# IR.net
KiCad netlist of a schematic drawn in Altium Designer
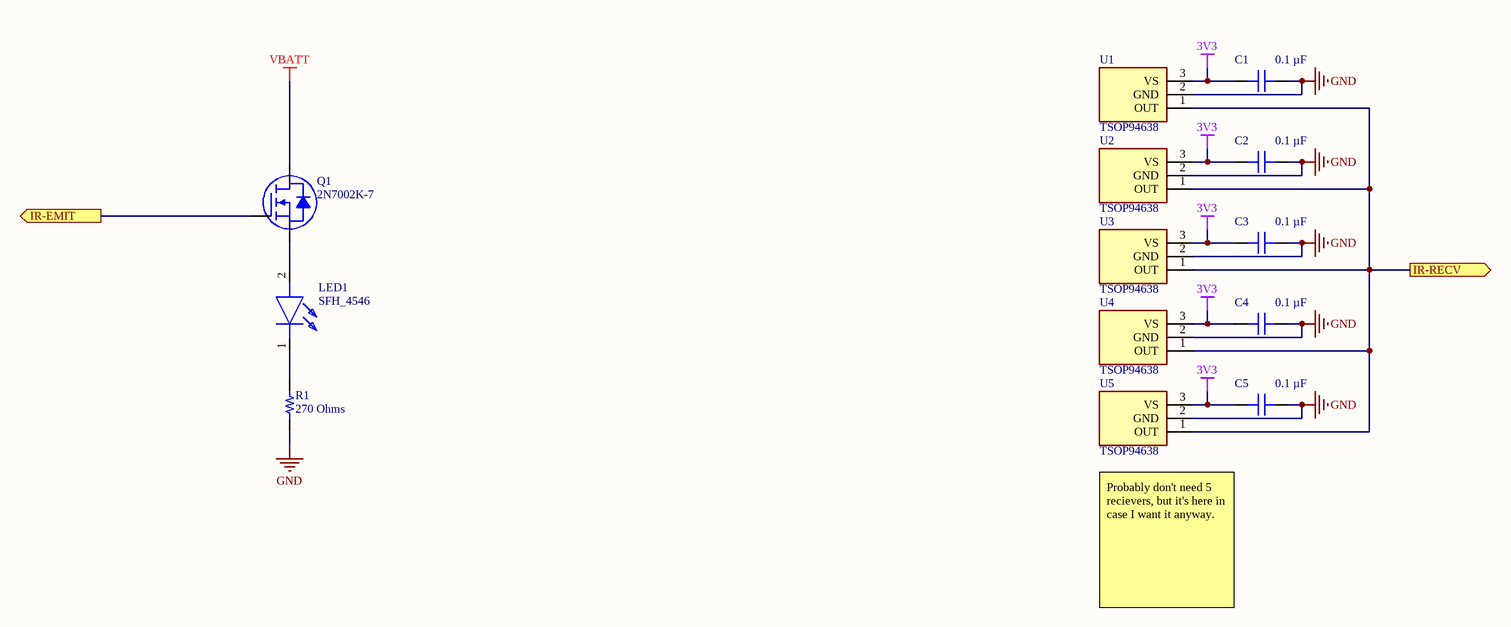
[diagram p0: IR.SchDoc]

(export (version "E")
  (design (tool "Eeschema 10.0.6"))
  (components
    (comp (ref "C1")
      (value "0.1 µF")
      (footprint "CAP 0805_2012")
      (description "CAP CER 0.1UF 25V X7R 0805")
      (fields
        (field (name "PART NUMBER") "0805B104K250CT")
        (field (name "CAPACITANCE") "0.1 µF")
        (field (name "MANUFACTURER") "Walsin Technology Corporation")
      )
      (libsource (lib "dblib") (part "Capacitor"))
    )
    (comp (ref "C2")
      (value "0.1 µF")
      (footprint "CAP 0805_2012")
      (description "CAP CER 0.1UF 25V X7R 0805")
      (fields
        (field (name "PART NUMBER") "0805B104K250CT")
        (field (name "CAPACITANCE") "0.1 µF")
        (field (name "MANUFACTURER") "Walsin Technology Corporation")
      )
      (libsource (lib "dblib") (part "Capacitor"))
    )
    (comp (ref "C3")
      (value "0.1 µF")
      (footprint "CAP 0805_2012")
      (description "CAP CER 0.1UF 25V X7R 0805")
      (fields
        (field (name "PART NUMBER") "0805B104K250CT")
        (field (name "CAPACITANCE") "0.1 µF")
        (field (name "MANUFACTURER") "Walsin Technology Corporation")
      )
      (libsource (lib "dblib") (part "Capacitor"))
    )
    (comp (ref "C4")
      (value "0.1 µF")
      (footprint "CAP 0805_2012")
      (description "CAP CER 0.1UF 25V X7R 0805")
      (fields
        (field (name "PART NUMBER") "0805B104K250CT")
        (field (name "CAPACITANCE") "0.1 µF")
        (field (name "MANUFACTURER") "Walsin Technology Corporation")
      )
      (libsource (lib "dblib") (part "Capacitor"))
    )
    (comp (ref "C5")
      (value "0.1 µF")
      (footprint "CAP 0805_2012")
      (description "CAP CER 0.1UF 25V X7R 0805")
      (fields
        (field (name "PART NUMBER") "0805B104K250CT")
        (field (name "CAPACITANCE") "0.1 µF")
        (field (name "MANUFACTURER") "Walsin Technology Corporation")
      )
      (libsource (lib "dblib") (part "Capacitor"))
    )
    (comp (ref "LED1")
      (value "SFH_4546")
      (footprint "SamacSys:SFH_4556P")
      (description "LED")
      (fields
        (field (name "MANUFACTURER_PART_NUMBER") "SFH 4546")
        (field (name "MOUSER PART NUMBER") "720-SFH4546")
      )
      (libsource (lib "*") (part "SFH_4546"))
    )
    (comp (ref "Q1")
      (value "2N7002K-7")
      (footprint "DIODES SOT-23-3")
      (description "MOSFET N-CH 60V 380MA SOT23-3")
      (fields (field (name "MANUFACTURER") "Diodes Incorporated"))
      (libsource (lib "dblib") (part "DIODES INC MOSFET N-CH SOT-23-3"))
    )
    (comp (ref "R1")
      (value "270 Ohms")
      (footprint "RES 0805_2012")
      (description "RES SMD 270 OHM 1% 1/8W 0805")
      (fields
        (field (name "PART NUMBER") "CRG0805F270R")
        (field (name "MANUFACTURER") "TE Connectivity Passive Product")
      )
      (libsource (lib "dblib") (part "Resistor"))
    )
    (comp (ref "U1")
      (value "TSOP94638")
      (footprint "SamacSys:TSOP94638")
      (description "Integrated Circuit")
      (fields (field (name "MOUSER PART NUMBER") "78-TSOP94638"))
      (libsource (lib "*") (part "TSOP94638"))
    )
    (comp (ref "U2")
      (value "TSOP94638")
      (footprint "SamacSys:TSOP94638")
      (description "Integrated Circuit")
      (fields (field (name "MOUSER PART NUMBER") "78-TSOP94638"))
      (libsource (lib "*") (part "TSOP94638"))
    )
    (comp (ref "U3")
      (value "TSOP94638")
      (footprint "SamacSys:TSOP94638")
      (description "Integrated Circuit")
      (fields (field (name "MOUSER PART NUMBER") "78-TSOP94638"))
      (libsource (lib "*") (part "TSOP94638"))
    )
    (comp (ref "U4")
      (value "TSOP94638")
      (footprint "SamacSys:TSOP94638")
      (description "Integrated Circuit")
      (fields (field (name "MOUSER PART NUMBER") "78-TSOP94638"))
      (libsource (lib "*") (part "TSOP94638"))
    )
    (comp (ref "U5")
      (value "TSOP94638")
      (footprint "SamacSys:TSOP94638")
      (description "Integrated Circuit")
      (fields (field (name "MOUSER PART NUMBER") "78-TSOP94638"))
      (libsource (lib "*") (part "TSOP94638"))
    )
  )
  (nets
    (net (code "1") (name "/IR-EMIT") (class "Default")
      (node (ref "Q1") (pin "1") (pinfunction "G_1") (pintype "passive"))
    )
    (net (code "2") (name "/IR-RECV") (class "Default")
      (node (ref "U1") (pin "1") (pinfunction "OUT_1") (pintype "passive"))
      (node (ref "U2") (pin "1") (pinfunction "OUT_1") (pintype "passive"))
      (node (ref "U3") (pin "1") (pinfunction "OUT_1") (pintype "passive"))
      (node (ref "U4") (pin "1") (pinfunction "OUT_1") (pintype "passive"))
      (node (ref "U5") (pin "1") (pinfunction "OUT_1") (pintype "passive"))
    )
    (net (code "3") (name "3V3") (class "Default")
      (node (ref "C1") (pin "2") (pinfunction "2_2") (pintype "passive"))
      (node (ref "C2") (pin "2") (pinfunction "2_2") (pintype "passive"))
      (node (ref "C3") (pin "2") (pinfunction "2_2") (pintype "passive"))
      (node (ref "C4") (pin "2") (pinfunction "2_2") (pintype "passive"))
      (node (ref "C5") (pin "2") (pinfunction "2_2") (pintype "passive"))
      (node (ref "U1") (pin "3") (pinfunction "VS_3") (pintype "passive"))
      (node (ref "U2") (pin "3") (pinfunction "VS_3") (pintype "passive"))
      (node (ref "U3") (pin "3") (pinfunction "VS_3") (pintype "passive"))
      (node (ref "U4") (pin "3") (pinfunction "VS_3") (pintype "passive"))
      (node (ref "U5") (pin "3") (pinfunction "VS_3") (pintype "passive"))
    )
    (net (code "4") (name "GND") (class "Default")
      (node (ref "C1") (pin "1") (pinfunction "1_1") (pintype "passive"))
      (node (ref "C2") (pin "1") (pinfunction "1_1") (pintype "passive"))
      (node (ref "C3") (pin "1") (pinfunction "1_1") (pintype "passive"))
      (node (ref "C4") (pin "1") (pinfunction "1_1") (pintype "passive"))
      (node (ref "C5") (pin "1") (pinfunction "1_1") (pintype "passive"))
      (node (ref "R1") (pin "1") (pinfunction "1_1") (pintype "passive"))
      (node (ref "U1") (pin "2") (pinfunction "GND_2") (pintype "passive"))
      (node (ref "U2") (pin "2") (pinfunction "GND_2") (pintype "passive"))
      (node (ref "U3") (pin "2") (pinfunction "GND_2") (pintype "passive"))
      (node (ref "U4") (pin "2") (pinfunction "GND_2") (pintype "passive"))
      (node (ref "U5") (pin "2") (pinfunction "GND_2") (pintype "passive"))
    )
    (net (code "5") (name "Net-(LED1-A)") (class "Default")
      (node (ref "LED1") (pin "2") (pinfunction "A_2") (pintype "passive"))
      (node (ref "Q1") (pin "2") (pinfunction "S_2") (pintype "passive"))
    )
    (net (code "6") (name "Net-(LED1-K)") (class "Default")
      (node (ref "LED1") (pin "1") (pinfunction "K_1") (pintype "passive"))
      (node (ref "R1") (pin "2") (pinfunction "2_2") (pintype "passive"))
    )
    (net (code "7") (name "VBATT") (class "Default")
      (node (ref "Q1") (pin "3") (pinfunction "D_3") (pintype "passive"))
    )
  )
)
